# MSP430_Main.net
KiCad netlist of a schematic drawn in Altium Designer
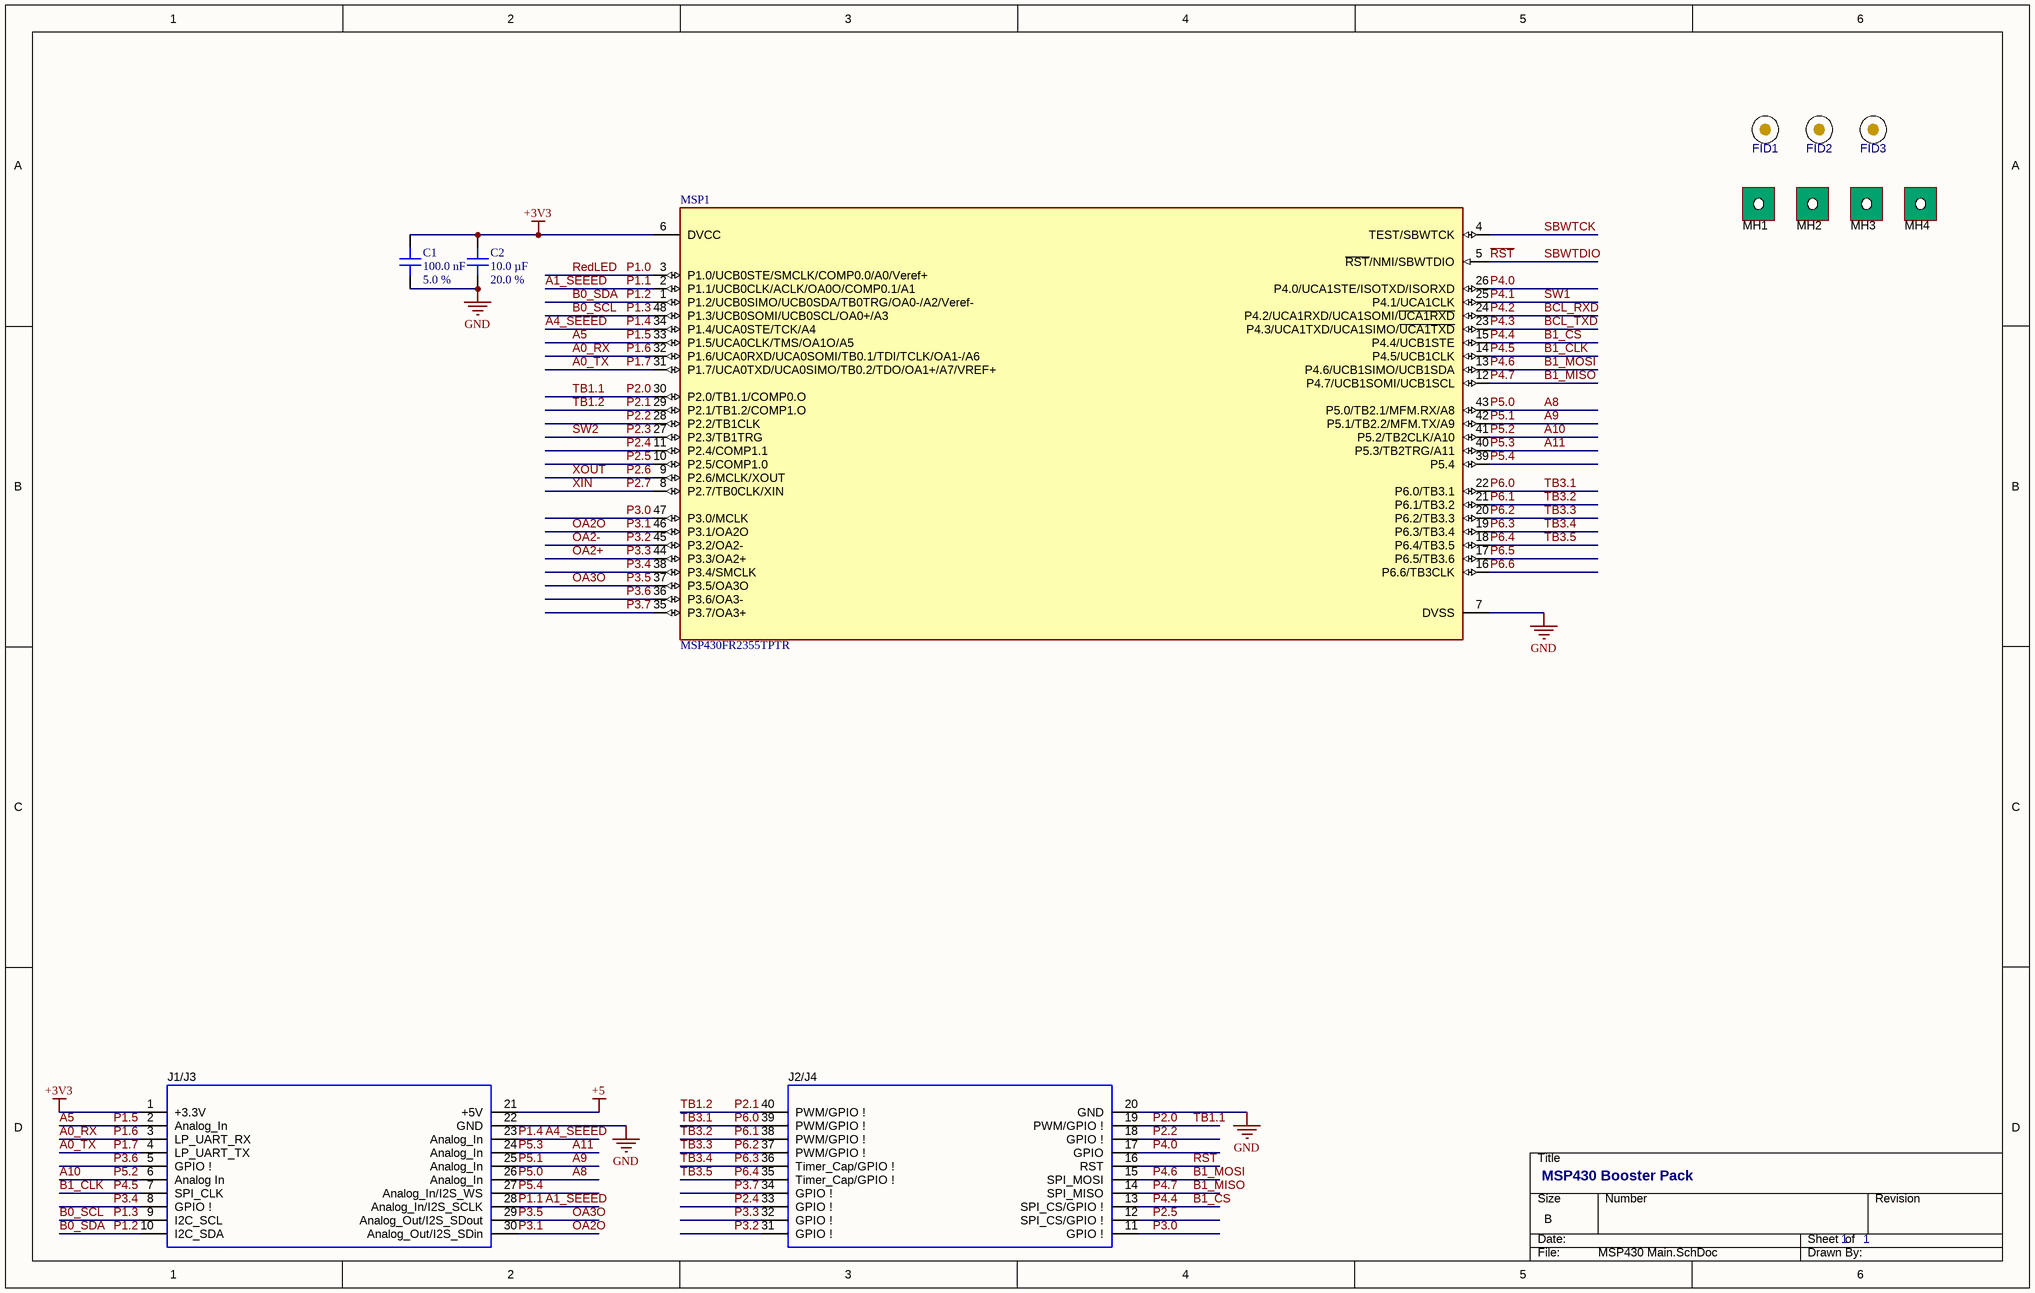
[diagram p0: MSP430 Main.SchDoc]

(export (version "E")
  (design (tool "Eeschema 10.0.6"))
  (components
    (comp (ref "C1")
      (value "100.0 nF")
      (footprint "PCB - CAPACITOR - MLCC - CAP 0603_1608")
      (description "0.1 µF ±5% 50V Ceramic Capacitor X7R 0603 (1608 Metric)")
      (fields
        (field (name "ROWAN PART NUMBER") "1564")
        (field (name "TOLERANCE") "5.0 %")
        (field (name "MANUFACTURER") "YAGEO")
      )
      (libsource (lib "RowanAltiumLibrary") (part "SCH - PASSIVES - CAPACITOR"))
    )
    (comp (ref "C2")
      (value "10.0 µF")
      (footprint "PCB - CAPACITOR - MLCC - CAP 0603_1608")
      (description "10 µF ±20% 16V Ceramic Capacitor X5R 0603 (1608 Metric)")
      (fields
        (field (name "ROWAN PART NUMBER") "1572")
        (field (name "TOLERANCE") "20.0 %")
        (field (name "MANUFACTURER") "YAGEO")
      )
      (libsource (lib "RowanAltiumLibrary") (part "SCH - PASSIVES - CAPACITOR"))
    )
    (comp (ref "FID1")
      (value "Fiducial")
      (footprint "Fiducial6.4-20")
      (description "Fiducial mark.  There is nothing to buy or mount.")
      (fields (field (name "SYMBOLCREATOR") "codlsc") (field (name "PUBLISHER") "Texas Instruments"))
      (libsource (lib "MiscParts") (part "Fiducial"))
    )
    (comp (ref "FID2")
      (value "Fiducial")
      (footprint "Fiducial6.4-20")
      (description "Fiducial mark.  There is nothing to buy or mount.")
      (fields (field (name "SYMBOLCREATOR") "codlsc") (field (name "PUBLISHER") "Texas Instruments"))
      (libsource (lib "MiscParts") (part "Fiducial"))
    )
    (comp (ref "FID3")
      (value "Fiducial")
      (footprint "Fiducial6.4-20")
      (description "Fiducial mark.  There is nothing to buy or mount.")
      (fields (field (name "SYMBOLCREATOR") "codlsc") (field (name "PUBLISHER") "Texas Instruments"))
      (libsource (lib "MiscParts") (part "Fiducial"))
    )
    (comp (ref "J1/J3")
      (value "SSQ-110-03-T-D")
      (footprint "BoosterPack_40pin_J1J3")
      (description "Receptacle, 2.54mm, 10x2, Tin, TH")
      (fields
        (field (name "MANUFACTURER") "Samtec")
        (field (name "ALTERNATE PARTNUMBER") "CRD-081413-A-G")
        (field (name "SYMBOLCREATOR") "a0412235")
        (field (name "PUBLISHER") "Texas Instruments")
      )
      (libsource (lib "Hardware") (part "BoosterPack_40pin_J1J3"))
    )
    (comp (ref "J2/J4")
      (value "SSQ-110-03-T-D")
      (footprint "BoosterPack_40pin_J2J4")
      (description "Receptacle, 2.54mm, 10x2, Tin, TH")
      (fields
        (field (name "MANUFACTURER") "Samtec")
        (field (name "ALTERNATE PARTNUMBER") "CRD-081413-A-G")
        (field (name "SYMBOLCREATOR") "a0412235")
        (field (name "PUBLISHER") "Texas Instruments")
      )
      (libsource (lib "Hardware") (part "BoosterPack_40pin_J2J4"))
    )
    (comp (ref "MH1")
      (value "MTG_NoPads")
      (footprint "NPTH125mil")
      (description "PCB Mounting Hole, No Pad")
      (fields
        (field (name "MANUFACTURER") "Any")
        (field (name "SYMBOLCREATOR") "a0412235")
        (field (name "PUBLISHER") "Texas Instruments")
      )
      (libsource (lib "Hardware") (part "Mounting Hole (non-standard) No Pad"))
    )
    (comp (ref "MH2")
      (value "MTG_NoPads")
      (footprint "NPTH125mil")
      (description "PCB Mounting Hole, No Pad")
      (fields
        (field (name "MANUFACTURER") "Any")
        (field (name "SYMBOLCREATOR") "a0412235")
        (field (name "PUBLISHER") "Texas Instruments")
      )
      (libsource (lib "Hardware") (part "Mounting Hole (non-standard) No Pad"))
    )
    (comp (ref "MH3")
      (value "MTG_NoPads")
      (footprint "NPTH125mil")
      (description "PCB Mounting Hole, No Pad")
      (fields
        (field (name "MANUFACTURER") "Any")
        (field (name "SYMBOLCREATOR") "a0412235")
        (field (name "PUBLISHER") "Texas Instruments")
      )
      (libsource (lib "Hardware") (part "Mounting Hole (non-standard) No Pad"))
    )
    (comp (ref "MH4")
      (value "MTG_NoPads")
      (footprint "NPTH125mil")
      (description "PCB Mounting Hole, No Pad")
      (fields
        (field (name "MANUFACTURER") "Any")
        (field (name "SYMBOLCREATOR") "a0412235")
        (field (name "PUBLISHER") "Texas Instruments")
      )
      (libsource (lib "Hardware") (part "Mounting Hole (non-standard) No Pad"))
    )
    (comp (ref "MSP1")
      (value "MSP430FR2355TPTR")
      (footprint "FP-PT0048A-MFG")
      (description "IC MCU 16BIT 32KB FRAM 48LQFP")
      (fields
        (field (name "MANUFACTURER") "Texas Instruments")
        (field (name "OCTOPART") "https://octopart.com/msp430fr2355tptr-texas+instruments-92191342")
      )
      (libsource (lib "Altium Content Vault") (part "bd983ca6877cdd146f198514b3acb3b"))
    )
  )
  (nets
    (net (code "1") (name "+3V3") (class "Default")
      (node (ref "C1") (pin "2") (pinfunction "2_2") (pintype "passive"))
      (node (ref "C2") (pin "2") (pinfunction "2_2") (pintype "passive"))
      (node (ref "J1/J3") (pin "1") (pinfunction "+3.3V_1") (pintype "power_in"))
      (node (ref "MSP1") (pin "6") (pinfunction "DVCC_6") (pintype "power_in"))
    )
    (net (code "2") (name "+5") (class "Default")
      (node (ref "J1/J3") (pin "21") (pinfunction "+5V_21") (pintype "power_in"))
    )
    (net (code "3") (name "/A0_RX") (class "Default")
      (node (ref "J1/J3") (pin "3") (pinfunction "LP_UART_RX_3") (pintype "passive"))
      (node (ref "MSP1") (pin "32") (pinfunction "P1.6/UCA0RXD/UCA0SOMI/TB0.1/TDI/TCLK/OA1-/A6_32") (pintype "bidirectional"))
    )
    (net (code "4") (name "/A0_TX") (class "Default")
      (node (ref "J1/J3") (pin "4") (pinfunction "LP_UART_TX_4") (pintype "passive"))
      (node (ref "MSP1") (pin "31") (pinfunction "P1.7/UCA0TXD/UCA0SIMO/TB0.2/TDO/OA1+/A7/VREF+_31") (pintype "bidirectional"))
    )
    (net (code "5") (name "/A1_SEEED") (class "Default")
      (node (ref "J1/J3") (pin "28") (pinfunction "Analog_In/I2S_SCLK_28") (pintype "passive"))
      (node (ref "MSP1") (pin "2") (pinfunction "P1.1/UCB0CLK/ACLK/OA0O/COMP0.1/A1_2") (pintype "bidirectional"))
    )
    (net (code "6") (name "/A4_SEEED") (class "Default")
      (node (ref "J1/J3") (pin "23") (pinfunction "Analog_In_23") (pintype "passive"))
      (node (ref "MSP1") (pin "34") (pinfunction "P1.4/UCA0STE/TCK/A4_34") (pintype "bidirectional"))
    )
    (net (code "7") (name "/A5") (class "Default")
      (node (ref "J1/J3") (pin "2") (pinfunction "Analog_In_2") (pintype "passive"))
      (node (ref "MSP1") (pin "33") (pinfunction "P1.5/UCA0CLK/TMS/OA1O/A5_33") (pintype "bidirectional"))
    )
    (net (code "8") (name "/A8") (class "Default")
      (node (ref "J1/J3") (pin "26") (pinfunction "Analog_In_26") (pintype "passive"))
      (node (ref "MSP1") (pin "43") (pinfunction "P5.0/TB2.1/MFM.RX/A8_43") (pintype "bidirectional"))
    )
    (net (code "9") (name "/A9") (class "Default")
      (node (ref "J1/J3") (pin "25") (pinfunction "Analog_In_25") (pintype "passive"))
      (node (ref "MSP1") (pin "42") (pinfunction "P5.1/TB2.2/MFM.TX/A9_42") (pintype "bidirectional"))
    )
    (net (code "10") (name "/A10") (class "Default")
      (node (ref "J1/J3") (pin "6") (pinfunction "Analog_In_6") (pintype "passive"))
      (node (ref "MSP1") (pin "41") (pinfunction "P5.2/TB2CLK/A10_41") (pintype "bidirectional"))
    )
    (net (code "11") (name "/A11") (class "Default")
      (node (ref "J1/J3") (pin "24") (pinfunction "Analog_In_24") (pintype "passive"))
      (node (ref "MSP1") (pin "40") (pinfunction "P5.3/TB2TRG/A11_40") (pintype "bidirectional"))
    )
    (net (code "12") (name "/B0_SCL") (class "Default")
      (node (ref "J1/J3") (pin "9") (pinfunction "I2C_SCL_9") (pintype "passive"))
      (node (ref "MSP1") (pin "48") (pinfunction "P1.3/UCB0SOMI/UCB0SCL/OA0+/A3_48") (pintype "bidirectional"))
    )
    (net (code "13") (name "/B0_SDA") (class "Default")
      (node (ref "J1/J3") (pin "10") (pinfunction "I2C_SDA_10") (pintype "passive"))
      (node (ref "MSP1") (pin "1") (pinfunction "P1.2/UCB0SIMO/UCB0SDA/TB0TRG/OA0-/A2/Veref-_1") (pintype "bidirectional"))
    )
    (net (code "14") (name "/B1_CLK") (class "Default")
      (node (ref "J1/J3") (pin "7") (pinfunction "SPI_CLK_7") (pintype "passive"))
      (node (ref "MSP1") (pin "14") (pinfunction "P4.5/UCB1CLK_14") (pintype "bidirectional"))
    )
    (net (code "15") (name "/B1_CS") (class "Default")
      (node (ref "J2/J4") (pin "13") (pinfunction "SPI_CS/GPIO_!_13") (pintype "passive"))
      (node (ref "MSP1") (pin "15") (pinfunction "P4.4/UCB1STE_15") (pintype "bidirectional"))
    )
    (net (code "16") (name "/B1_MISO") (class "Default")
      (node (ref "J2/J4") (pin "14") (pinfunction "SPI_MISO_14") (pintype "passive"))
      (node (ref "MSP1") (pin "12") (pinfunction "P4.7/UCB1SOMI/UCB1SCL_12") (pintype "bidirectional"))
    )
    (net (code "17") (name "/B1_MOSI") (class "Default")
      (node (ref "J2/J4") (pin "15") (pinfunction "SPI_MOSI_15") (pintype "passive"))
      (node (ref "MSP1") (pin "13") (pinfunction "P4.6/UCB1SIMO/UCB1SDA_13") (pintype "bidirectional"))
    )
    (net (code "18") (name "/BCL_RXD") (class "Default")
      (node (ref "MSP1") (pin "24") (pinfunction "P4.2/UCA1RXD/UCA1SOMI/~{UCA1RXD}_24") (pintype "bidirectional"))
    )
    (net (code "19") (name "/BCL_TXD") (class "Default")
      (node (ref "MSP1") (pin "23") (pinfunction "P4.3/UCA1TXD/UCA1SIMO/~{UCA1TXD}_23") (pintype "bidirectional"))
    )
    (net (code "20") (name "/OA2+") (class "Default")
      (node (ref "J2/J4") (pin "32") (pinfunction "GPIO_!_32") (pintype "passive"))
      (node (ref "MSP1") (pin "44") (pinfunction "P3.3/OA2+_44") (pintype "bidirectional"))
    )
    (net (code "21") (name "/OA2-") (class "Default")
      (node (ref "J2/J4") (pin "31") (pinfunction "GPIO_!_31") (pintype "passive"))
      (node (ref "MSP1") (pin "45") (pinfunction "P3.2/OA2-_45") (pintype "bidirectional"))
    )
    (net (code "22") (name "/OA2O") (class "Default")
      (node (ref "J1/J3") (pin "30") (pinfunction "Analog_Out/I2S_SDin_30") (pintype "passive"))
      (node (ref "MSP1") (pin "46") (pinfunction "P3.1/OA2O_46") (pintype "bidirectional"))
    )
    (net (code "23") (name "/OA3O") (class "Default")
      (node (ref "J1/J3") (pin "29") (pinfunction "Analog_Out/I2S_SDout_29") (pintype "passive"))
      (node (ref "MSP1") (pin "37") (pinfunction "P3.5/OA3O_37") (pintype "bidirectional"))
    )
    (net (code "24") (name "/P1.0") (class "Default")
      (node (ref "MSP1") (pin "3") (pinfunction "P1.0/UCB0STE/SMCLK/COMP0.0/A0/Veref+_3") (pintype "bidirectional"))
    )
    (net (code "25") (name "/P2.0") (class "Default")
      (node (ref "J2/J4") (pin "19") (pinfunction "PWM/GPIO_!_19") (pintype "passive"))
      (node (ref "MSP1") (pin "30") (pinfunction "P2.0/TB1.1/COMP0.O_30") (pintype "bidirectional"))
    )
    (net (code "26") (name "/P2.1") (class "Default")
      (node (ref "J2/J4") (pin "40") (pinfunction "PWM/GPIO_!_40") (pintype "passive"))
      (node (ref "MSP1") (pin "29") (pinfunction "P2.1/TB1.2/COMP1.O_29") (pintype "bidirectional"))
    )
    (net (code "27") (name "/P2.2") (class "Default")
      (node (ref "J2/J4") (pin "18") (pinfunction "GPIO_!_18") (pintype "passive"))
      (node (ref "MSP1") (pin "28") (pinfunction "P2.2/TB1CLK_28") (pintype "bidirectional"))
    )
    (net (code "28") (name "/P2.3") (class "Default")
      (node (ref "MSP1") (pin "27") (pinfunction "P2.3/TB1TRG_27") (pintype "bidirectional"))
    )
    (net (code "29") (name "/P2.4") (class "Default")
      (node (ref "J2/J4") (pin "33") (pinfunction "GPIO_!_33") (pintype "passive"))
      (node (ref "MSP1") (pin "11") (pinfunction "P2.4/COMP1.1_11") (pintype "bidirectional"))
    )
    (net (code "30") (name "/P2.5") (class "Default")
      (node (ref "J2/J4") (pin "12") (pinfunction "SPI_CS/GPIO_!_12") (pintype "passive"))
      (node (ref "MSP1") (pin "10") (pinfunction "P2.5/COMP1.0_10") (pintype "bidirectional"))
    )
    (net (code "31") (name "/P2.6") (class "Default")
      (node (ref "MSP1") (pin "9") (pinfunction "P2.6/MCLK/XOUT_9") (pintype "bidirectional"))
    )
    (net (code "32") (name "/P2.7") (class "Default")
      (node (ref "MSP1") (pin "8") (pinfunction "P2.7/TB0CLK/XIN_8") (pintype "bidirectional"))
    )
    (net (code "33") (name "/P3.0") (class "Default")
      (node (ref "J2/J4") (pin "11") (pinfunction "GPIO_!_11") (pintype "passive"))
      (node (ref "MSP1") (pin "47") (pinfunction "P3.0/MCLK_47") (pintype "bidirectional"))
    )
    (net (code "34") (name "/P3.4") (class "Default")
      (node (ref "J1/J3") (pin "8") (pinfunction "GPIO_!_8") (pintype "passive"))
      (node (ref "MSP1") (pin "38") (pinfunction "P3.4/SMCLK_38") (pintype "bidirectional"))
    )
    (net (code "35") (name "/P3.6") (class "Default")
      (node (ref "J1/J3") (pin "5") (pinfunction "GPIO_!_5") (pintype "passive"))
      (node (ref "MSP1") (pin "36") (pinfunction "P3.6/OA3-_36") (pintype "bidirectional"))
    )
    (net (code "36") (name "/P3.7") (class "Default")
      (node (ref "J2/J4") (pin "34") (pinfunction "GPIO_!_34") (pintype "passive"))
      (node (ref "MSP1") (pin "35") (pinfunction "P3.7/OA3+_35") (pintype "bidirectional"))
    )
    (net (code "37") (name "/P4.0") (class "Default")
      (node (ref "J2/J4") (pin "17") (pinfunction "GPIO_17") (pintype "passive"))
      (node (ref "MSP1") (pin "26") (pinfunction "P4.0/UCA1STE/ISOTXD/ISORXD_26") (pintype "bidirectional"))
    )
    (net (code "38") (name "/P4.1") (class "Default")
      (node (ref "MSP1") (pin "25") (pinfunction "P4.1/UCA1CLK_25") (pintype "bidirectional"))
    )
    (net (code "39") (name "/P5.4") (class "Default")
      (node (ref "J1/J3") (pin "27") (pinfunction "Analog_In/I2S_WS_27") (pintype "passive"))
      (node (ref "MSP1") (pin "39") (pinfunction "P5.4_39") (pintype "bidirectional"))
    )
    (net (code "40") (name "/P6.0") (class "Default")
      (node (ref "J2/J4") (pin "39") (pinfunction "PWM/GPIO_!_39") (pintype "passive"))
      (node (ref "MSP1") (pin "22") (pinfunction "P6.0/TB3.1_22") (pintype "bidirectional"))
    )
    (net (code "41") (name "/P6.1") (class "Default")
      (node (ref "J2/J4") (pin "38") (pinfunction "PWM/GPIO_!_38") (pintype "passive"))
      (node (ref "MSP1") (pin "21") (pinfunction "P6.1/TB3.2_21") (pintype "bidirectional"))
    )
    (net (code "42") (name "/P6.2") (class "Default")
      (node (ref "J2/J4") (pin "37") (pinfunction "PWM/GPIO_!_37") (pintype "passive"))
      (node (ref "MSP1") (pin "20") (pinfunction "P6.2/TB3.3_20") (pintype "bidirectional"))
    )
    (net (code "43") (name "/P6.3") (class "Default")
      (node (ref "J2/J4") (pin "36") (pinfunction "Timer_Cap/GPIO_!_36") (pintype "passive"))
      (node (ref "MSP1") (pin "19") (pinfunction "P6.3/TB3.4_19") (pintype "bidirectional"))
    )
    (net (code "44") (name "/P6.4") (class "Default")
      (node (ref "J2/J4") (pin "35") (pinfunction "Timer_Cap/GPIO_!_35") (pintype "passive"))
      (node (ref "MSP1") (pin "18") (pinfunction "P6.4/TB3.5_18") (pintype "bidirectional"))
    )
    (net (code "45") (name "/P6.5") (class "Default")
      (node (ref "MSP1") (pin "17") (pinfunction "P6.5/TB3.6_17") (pintype "bidirectional"))
    )
    (net (code "46") (name "/P6.6") (class "Default")
      (node (ref "MSP1") (pin "16") (pinfunction "P6.6/TB3CLK_16") (pintype "bidirectional"))
    )
    (net (code "47") (name "/SBWTCK") (class "Default")
      (node (ref "MSP1") (pin "4") (pinfunction "TEST/SBWTCK_4") (pintype "bidirectional"))
    )
    (net (code "48") (name "/SBWTDIO") (class "Default")
      (node (ref "J2/J4") (pin "16") (pinfunction "RST_16") (pintype "passive"))
      (node (ref "MSP1") (pin "5") (pinfunction "~{RST}/NMI/SBWTDIO_5") (pintype "input"))
    )
    (net (code "49") (name "GND") (class "Default")
      (node (ref "C1") (pin "1") (pinfunction "1_1") (pintype "passive"))
      (node (ref "C2") (pin "1") (pinfunction "1_1") (pintype "passive"))
      (node (ref "J1/J3") (pin "22") (pinfunction "GND_22") (pintype "power_in"))
      (node (ref "J2/J4") (pin "20") (pinfunction "GND_20") (pintype "power_in"))
      (node (ref "MSP1") (pin "7") (pinfunction "DVSS_7") (pintype "power_in"))
    )
  )
)
